# outputs.net
KiCad netlist of a schematic drawn in Altium Designer
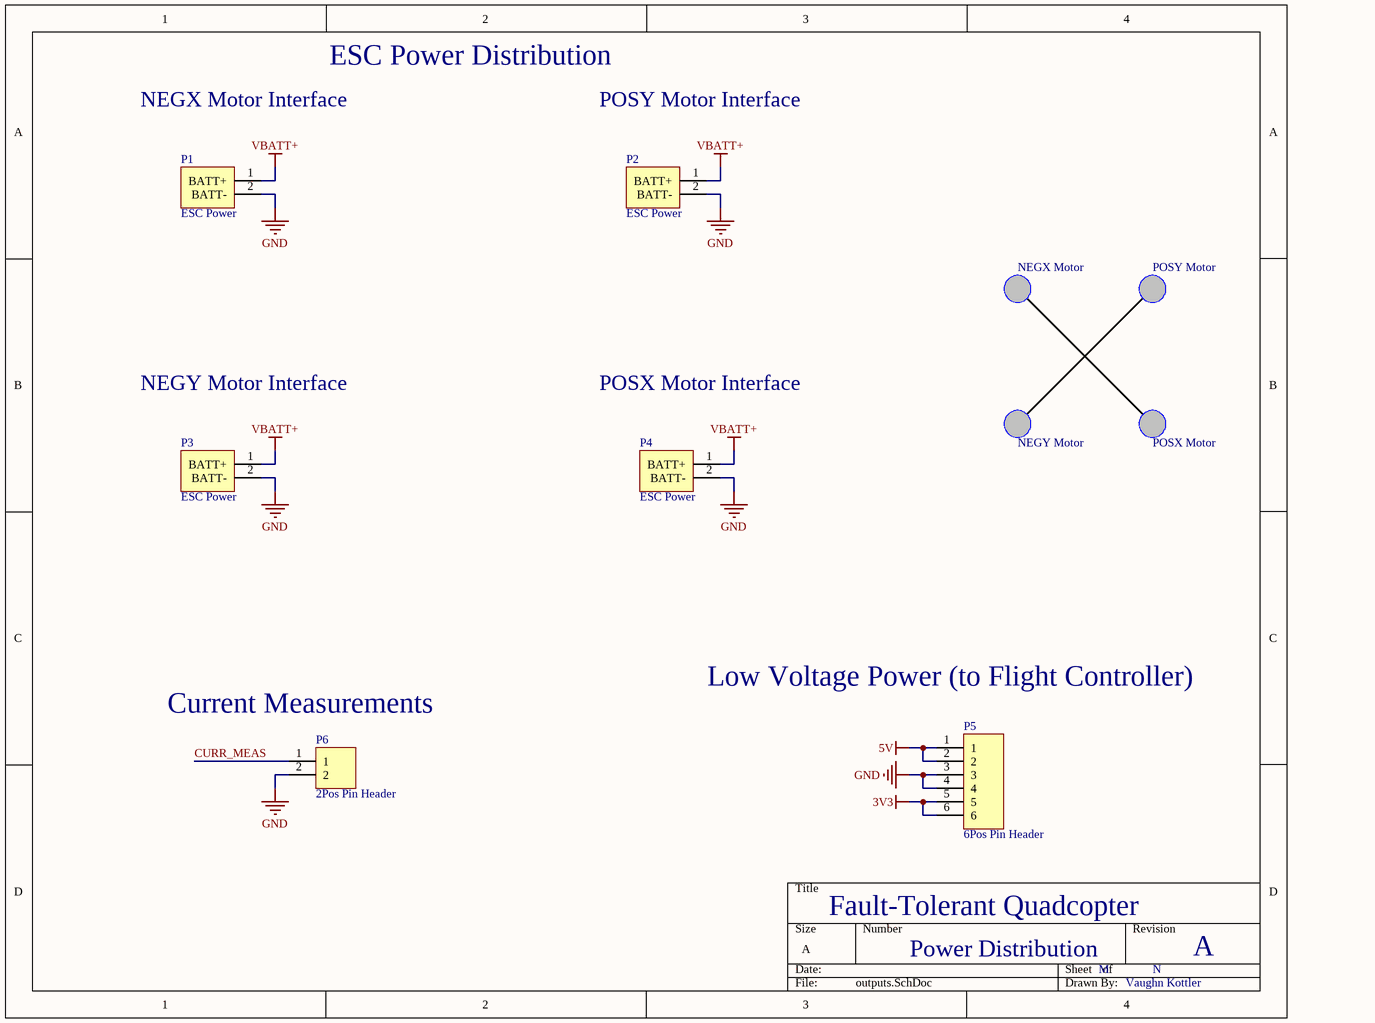
[diagram p0: outputs.SchDoc]

(export (version "E")
  (design (tool "Eeschema 10.0.6"))
  (components
    (comp (ref "P1")
      (value "ESC Power")
      (footprint "2Pos Screw Terminal")
      (description "0.2\" Pitch 1x2")
      (libsource (lib "connector") (part "ESC Power"))
    )
    (comp (ref "P2")
      (value "ESC Power")
      (footprint "2Pos Screw Terminal")
      (description "0.2\" Pitch 1x2")
      (libsource (lib "connector") (part "ESC Power"))
    )
    (comp (ref "P3")
      (value "ESC Power")
      (footprint "2Pos Screw Terminal")
      (description "0.2\" Pitch 1x2")
      (libsource (lib "connector") (part "ESC Power"))
    )
    (comp (ref "P4")
      (value "ESC Power")
      (footprint "2Pos Screw Terminal")
      (description "0.2\" Pitch 1x2")
      (libsource (lib "connector") (part "ESC Power"))
    )
    (comp (ref "P5")
      (value "6Pos Pin Header")
      (footprint "6Pos Pin Header JST")
      (description "0.1\" Pitch 1x6")
      (libsource (lib "connector") (part "6Pos Pin Header"))
    )
    (comp (ref "P6")
      (value "2Pos Pin Header")
      (footprint "2Pos Pin Header JST")
      (description "0.1\" Pitch 1x2")
      (libsource (lib "connector") (part "2Pos Pin Header"))
    )
  )
  (nets
    (net (code "1") (name "/CURR_MEAS") (class "Default")
      (node (ref "P6") (pin "1") (pinfunction "1_1") (pintype "passive"))
    )
    (net (code "2") (name "3V3") (class "Default")
      (node (ref "P5") (pin "5") (pinfunction "5_5") (pintype "passive"))
      (node (ref "P5") (pin "6") (pinfunction "6_6") (pintype "passive"))
    )
    (net (code "3") (name "5V") (class "Default")
      (node (ref "P5") (pin "1") (pinfunction "1_1") (pintype "passive"))
      (node (ref "P5") (pin "2") (pinfunction "2_2") (pintype "passive"))
    )
    (net (code "4") (name "GND") (class "Default")
      (node (ref "P1") (pin "2") (pinfunction "BATT-_2") (pintype "passive"))
      (node (ref "P2") (pin "2") (pinfunction "BATT-_2") (pintype "passive"))
      (node (ref "P3") (pin "2") (pinfunction "BATT-_2") (pintype "passive"))
      (node (ref "P4") (pin "2") (pinfunction "BATT-_2") (pintype "passive"))
      (node (ref "P5") (pin "3") (pinfunction "3_3") (pintype "passive"))
      (node (ref "P5") (pin "4") (pinfunction "4_4") (pintype "passive"))
      (node (ref "P6") (pin "2") (pinfunction "2_2") (pintype "passive"))
    )
    (net (code "5") (name "VBATT+") (class "Default")
      (node (ref "P1") (pin "1") (pinfunction "BATT+_1") (pintype "passive"))
      (node (ref "P2") (pin "1") (pinfunction "BATT+_1") (pintype "passive"))
      (node (ref "P3") (pin "1") (pinfunction "BATT+_1") (pintype "passive"))
      (node (ref "P4") (pin "1") (pinfunction "BATT+_1") (pintype "passive"))
    )
  )
)
